# Interface.net
KiCad netlist of a schematic drawn in Altium Designer
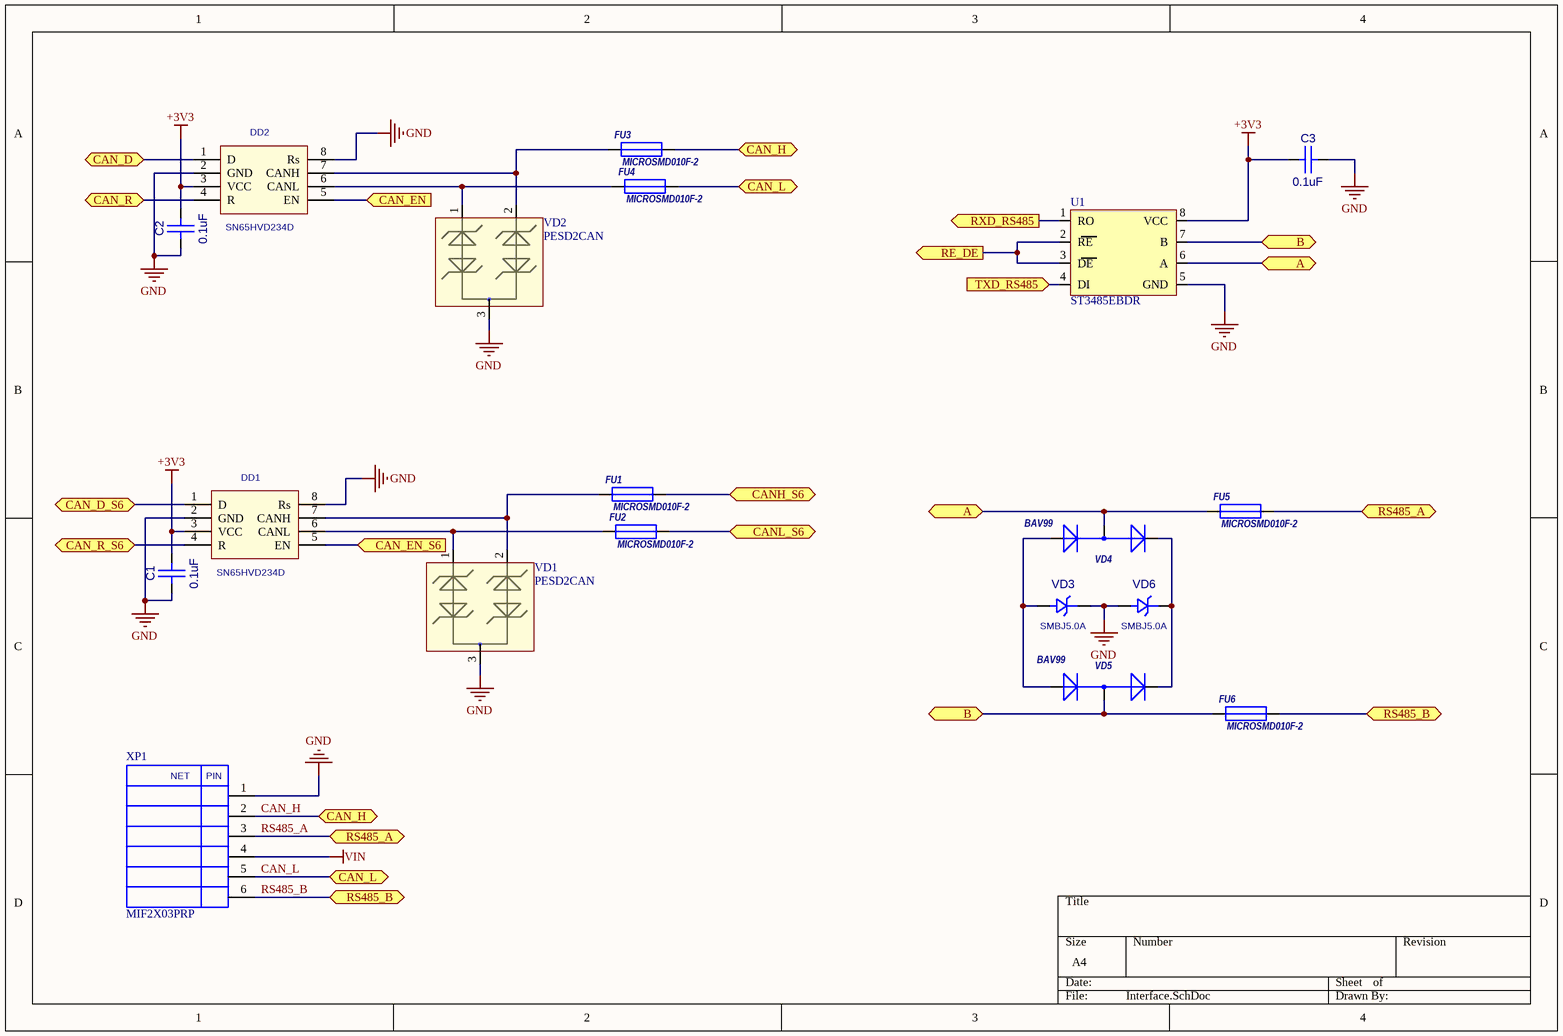
[diagram p0: Interface.SchDoc]

(export (version "E")
  (design (tool "Eeschema 10.0.6"))
  (components
    (comp (ref "C1")
      (value "0.1uF")
      (footprint "CC0603-3M")
      (description "CC0603")
      (libsource (lib "gprs_modem") (part "CC0603"))
    )
    (comp (ref "C2")
      (value "0.1uF")
      (footprint "CC0603-3M")
      (description "CC0603")
      (libsource (lib "gprs_modem") (part "CC0603"))
    )
    (comp (ref "C3")
      (value "0.1uF")
      (footprint "CC0603-3M")
      (description "CC0603")
      (libsource (lib "Schetchik") (part "CC0603"))
    )
    (comp (ref "DD1")
      (value "SN65HVD234D")
      (footprint "SO-8")
      (description "CAN Transceiver")
      (libsource (lib "gprs_modem") (part "SN65HVD234D"))
    )
    (comp (ref "DD2")
      (value "SN65HVD234D")
      (footprint "SO-8")
      (description "CAN Transceiver")
      (libsource (lib "gprs_modem") (part "SN65HVD234D"))
    )
    (comp (ref "FU1")
      (value "MICROSMD010F-2")
      (footprint "RC1210")
      (description "MICROSMD")
      (libsource (lib "gprs_modem") (part "MICROSMD"))
    )
    (comp (ref "FU2")
      (value "MICROSMD010F-2")
      (footprint "RC1210")
      (description "MICROSMD")
      (libsource (lib "gprs_modem") (part "MICROSMD"))
    )
    (comp (ref "FU3")
      (value "MICROSMD010F-2")
      (footprint "RC1210")
      (description "MICROSMD")
      (libsource (lib "gprs_modem") (part "MICROSMD"))
    )
    (comp (ref "FU4")
      (value "MICROSMD010F-2")
      (footprint "RC1210")
      (description "MICROSMD")
      (libsource (lib "gprs_modem") (part "MICROSMD"))
    )
    (comp (ref "FU5")
      (value "MICROSMD010F-2")
      (footprint "RC1210")
      (description "MICROSMD")
      (libsource (lib "Schetchik") (part "MICROSMD"))
    )
    (comp (ref "FU6")
      (value "MICROSMD010F-2")
      (footprint "RC1210")
      (description "MICROSMD")
      (libsource (lib "Schetchik") (part "MICROSMD"))
    )
    (comp (ref "U1") (value "ST3485EBDR") (footprint "SO-8") (libsource (lib "VHF") (part "ST3485EBDR")))
    (comp (ref "VD1")
      (value "PESD2CAN")
      (footprint "SOT-23(123)")
      (description "TVS for CAN")
      (libsource (lib "gprs_modem") (part "PESD2CAN"))
    )
    (comp (ref "VD2")
      (value "PESD2CAN")
      (footprint "SOT-23(123)")
      (description "TVS for CAN")
      (libsource (lib "gprs_modem") (part "PESD2CAN"))
    )
    (comp (ref "VD3")
      (value "SMBJ5.0A")
      (footprint "SMB")
      (description "SMBJ")
      (libsource (lib "gprs_modem") (part "SMBJ"))
    )
    (comp (ref "VD4")
      (value "BAV99")
      (footprint "SOT-23(GSD)")
      (description "1.0 Ampere General Purpose Rectifier")
      (libsource (lib "gprs_modem") (part "BAV99"))
    )
    (comp (ref "VD5")
      (value "BAV99")
      (footprint "SOT-23(GSD)")
      (description "1.0 Ampere General Purpose Rectifier")
      (libsource (lib "gprs_modem") (part "BAV99"))
    )
    (comp (ref "VD6")
      (value "SMBJ5.0A")
      (footprint "SMB")
      (description "SMBJ")
      (libsource (lib "gprs_modem") (part "SMBJ"))
    )
    (comp (ref "XP1")
      (value "MIF2X03PRP")
      (footprint "MIF2X03PRP")
      (description "MIF2x03PRP")
      (libsource (lib "gprs_modem") (part "MIF2X03PRP"))
    )
  )
  (nets
    (net (code "1") (name "+3V3") (class "Default")
      (node (ref "C1") (pin "2") (pinfunction "B_2") (pintype "passive"))
      (node (ref "C2") (pin "2") (pinfunction "B_2") (pintype "passive"))
      (node (ref "C3") (pin "1") (pinfunction "A_1") (pintype "passive"))
      (node (ref "DD1") (pin "3") (pinfunction "VCC_3") (pintype "passive"))
      (node (ref "DD2") (pin "3") (pinfunction "VCC_3") (pintype "passive"))
      (node (ref "U1") (pin "8") (pinfunction "VCC_8") (pintype "passive"))
    )
    (net (code "2") (name "/A") (class "Default")
      (node (ref "FU5") (pin "1") (pintype "passive"))
      (node (ref "U1") (pin "6") (pinfunction "A_6") (pintype "passive"))
      (node (ref "VD4") (pin "3") (pinfunction "AK_3") (pintype "passive"))
    )
    (net (code "3") (name "/B") (class "Default")
      (node (ref "FU6") (pin "1") (pintype "passive"))
      (node (ref "U1") (pin "7") (pinfunction "B_7") (pintype "passive"))
      (node (ref "VD5") (pin "3") (pinfunction "AK_3") (pintype "passive"))
    )
    (net (code "4") (name "/CANH_S6") (class "Default") (node (ref "FU1") (pin "2") (pintype "passive")))
    (net (code "5") (name "/CANL_S6") (class "Default") (node (ref "FU2") (pin "2") (pintype "passive")))
    (net (code "6") (name "/CAN_D") (class "Default")
      (node (ref "DD2") (pin "1") (pinfunction "D_1") (pintype "passive"))
    )
    (net (code "7") (name "/CAN_D_S6") (class "Default")
      (node (ref "DD1") (pin "1") (pinfunction "D_1") (pintype "passive"))
    )
    (net (code "8") (name "/CAN_EN") (class "Default")
      (node (ref "DD2") (pin "5") (pinfunction "EN_5") (pintype "passive"))
    )
    (net (code "9") (name "/CAN_EN_S6") (class "Default")
      (node (ref "DD1") (pin "5") (pinfunction "EN_5") (pintype "passive"))
    )
    (net (code "10") (name "/CAN_H") (class "Default")
      (node (ref "FU3") (pin "2") (pintype "passive"))
      (node (ref "XP1") (pin "2") (pinfunction "2_2") (pintype "passive"))
    )
    (net (code "11") (name "/CAN_L") (class "Default")
      (node (ref "FU4") (pin "2") (pintype "passive"))
      (node (ref "XP1") (pin "5") (pinfunction "5_5") (pintype "passive"))
    )
    (net (code "12") (name "/CAN_R") (class "Default")
      (node (ref "DD2") (pin "4") (pinfunction "R_4") (pintype "passive"))
    )
    (net (code "13") (name "/CAN_R_S6") (class "Default")
      (node (ref "DD1") (pin "4") (pinfunction "R_4") (pintype "passive"))
    )
    (net (code "14") (name "/RE_DE") (class "Default")
      (node (ref "U1") (pin "2") (pinfunction "RE_2") (pintype "passive"))
      (node (ref "U1") (pin "3") (pinfunction "DE_3") (pintype "passive"))
    )
    (net (code "15") (name "/RS485_A") (class "Default")
      (node (ref "FU5") (pin "2") (pintype "passive"))
      (node (ref "XP1") (pin "3") (pinfunction "3_3") (pintype "passive"))
    )
    (net (code "16") (name "/RS485_B") (class "Default")
      (node (ref "FU6") (pin "2") (pintype "passive"))
      (node (ref "XP1") (pin "6") (pinfunction "6_6") (pintype "passive"))
    )
    (net (code "17") (name "/RXD_RS485") (class "Default")
      (node (ref "U1") (pin "1") (pinfunction "RO_1") (pintype "passive"))
    )
    (net (code "18") (name "/TXD_RS485") (class "Default")
      (node (ref "U1") (pin "4") (pinfunction "DI_4") (pintype "passive"))
    )
    (net (code "19") (name "GND") (class "Default")
      (node (ref "C1") (pin "1") (pinfunction "A_1") (pintype "passive"))
      (node (ref "C2") (pin "1") (pinfunction "A_1") (pintype "passive"))
      (node (ref "C3") (pin "2") (pinfunction "B_2") (pintype "passive"))
      (node (ref "DD1") (pin "2") (pinfunction "GND_2") (pintype "passive"))
      (node (ref "DD1") (pin "8") (pinfunction "Rs_8") (pintype "passive"))
      (node (ref "DD2") (pin "2") (pinfunction "GND_2") (pintype "passive"))
      (node (ref "DD2") (pin "8") (pinfunction "Rs_8") (pintype "passive"))
      (node (ref "U1") (pin "5") (pinfunction "GND_5") (pintype "passive"))
      (node (ref "VD1") (pin "3") (pinfunction "3_3") (pintype "passive"))
      (node (ref "VD2") (pin "3") (pinfunction "3_3") (pintype "passive"))
      (node (ref "VD3") (pin "2") (pinfunction "K_2") (pintype "passive"))
      (node (ref "VD6") (pin "1") (pinfunction "A_1") (pintype "passive"))
      (node (ref "XP1") (pin "1") (pinfunction "1_1") (pintype "passive"))
    )
    (net (code "20") (name "Net-(DD1-CANH)") (class "Default")
      (node (ref "DD1") (pin "7") (pinfunction "CANH_7") (pintype "passive"))
      (node (ref "FU1") (pin "1") (pintype "passive"))
      (node (ref "VD1") (pin "2") (pinfunction "2_2") (pintype "passive"))
    )
    (net (code "21") (name "Net-(DD1-CANL)") (class "Default")
      (node (ref "DD1") (pin "6") (pinfunction "CANL_6") (pintype "passive"))
      (node (ref "FU2") (pin "1") (pintype "passive"))
      (node (ref "VD1") (pin "1") (pinfunction "1_1") (pintype "passive"))
    )
    (net (code "22") (name "Net-(DD2-CANH)") (class "Default")
      (node (ref "DD2") (pin "7") (pinfunction "CANH_7") (pintype "passive"))
      (node (ref "FU3") (pin "1") (pintype "passive"))
      (node (ref "VD2") (pin "2") (pinfunction "2_2") (pintype "passive"))
    )
    (net (code "23") (name "Net-(DD2-CANL)") (class "Default")
      (node (ref "DD2") (pin "6") (pinfunction "CANL_6") (pintype "passive"))
      (node (ref "FU4") (pin "1") (pintype "passive"))
      (node (ref "VD2") (pin "1") (pinfunction "1_1") (pintype "passive"))
    )
    (net (code "24") (name "Net-(VD3-A)") (class "Default")
      (node (ref "VD3") (pin "1") (pinfunction "A_1") (pintype "passive"))
      (node (ref "VD4") (pin "1") (pinfunction "A_1") (pintype "passive"))
      (node (ref "VD5") (pin "1") (pinfunction "A_1") (pintype "passive"))
    )
    (net (code "25") (name "Net-(VD4-K)") (class "Default")
      (node (ref "VD4") (pin "2") (pinfunction "K_2") (pintype "passive"))
      (node (ref "VD5") (pin "2") (pinfunction "K_2") (pintype "passive"))
      (node (ref "VD6") (pin "2") (pinfunction "K_2") (pintype "passive"))
    )
    (net (code "26") (name "VIN") (class "Default")
      (node (ref "XP1") (pin "4") (pinfunction "4_4") (pintype "passive"))
    )
  )
)
